# Temperature.net
KiCad netlist of a schematic drawn in Altium Designer
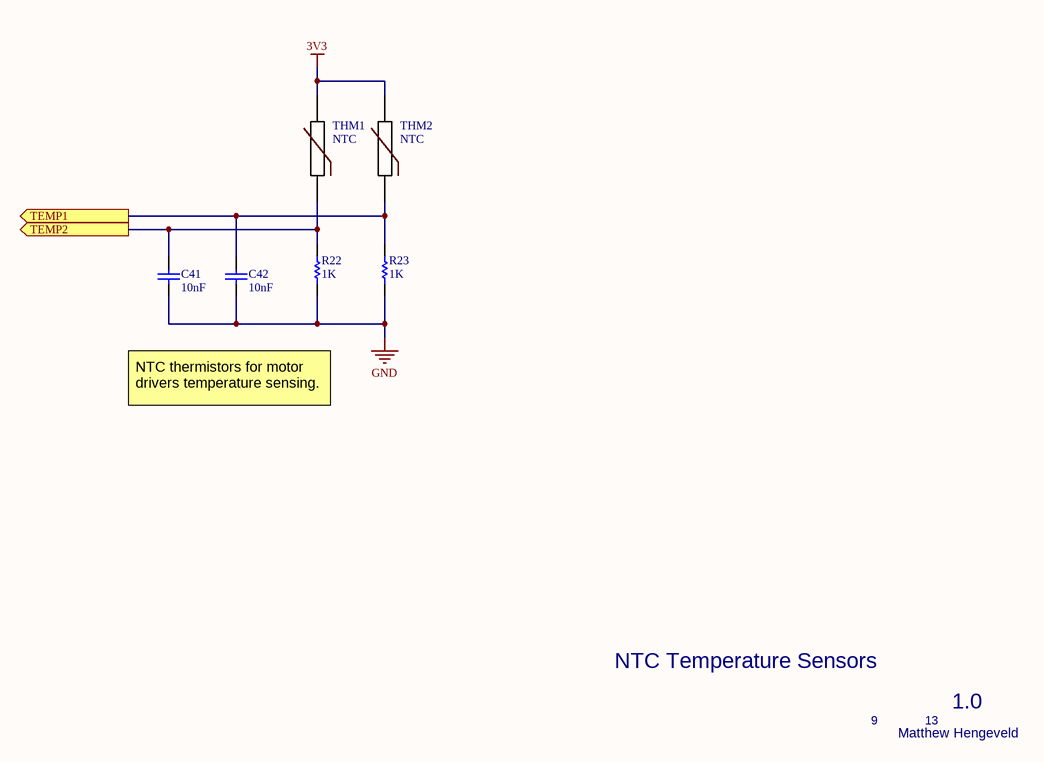
[diagram p0: Temperature.SchDoc]

(export (version "E")
  (design (tool "Eeschema 10.0.6"))
  (components
    (comp (ref "C41")
      (value "10nF")
      (footprint "CAPC1608X92X38LL15T08")
      (fields (field (name "PART NUMBER") "VJ0603Y104KNXAO") (field (name "MANUFACTURER") "Vitramon"))
      (libsource (lib "Altium Content Vault") (part "CAP"))
    )
    (comp (ref "C42")
      (value "10nF")
      (footprint "CAPC1608X92X38LL15T08")
      (fields (field (name "PART NUMBER") "VJ0603Y104KNXAO") (field (name "MANUFACTURER") "Vitramon"))
      (libsource (lib "Altium Content Vault") (part "CAP"))
    )
    (comp (ref "R22")
      (value "1K")
      (footprint "RESC1608X55X30LL15T15")
      (fields (field (name "MANUFACTURER") "Panasonic") (field (name "PART NUMBER") "ERJ-3GEYJ103V"))
      (libsource (lib "Altium Content Vault") (part "RES"))
    )
    (comp (ref "R23")
      (value "1K")
      (footprint "RESC1608X55X30LL15T15")
      (fields (field (name "MANUFACTURER") "Panasonic") (field (name "PART NUMBER") "ERJ-3GEYJ103V"))
      (libsource (lib "Altium Content Vault") (part "RES"))
    )
    (comp (ref "THM1") (value "NTC") (footprint "NTC") (libsource (lib "Hengeveld") (part "NTC")))
    (comp (ref "THM2") (value "NTC") (footprint "NTC") (libsource (lib "Hengeveld") (part "NTC")))
  )
  (nets
    (net (code "1") (name "/TEMP1") (class "Default")
      (node (ref "C42") (pin "2") (pinfunction "2_2") (pintype "passive"))
      (node (ref "R23") (pin "2") (pinfunction "2_2") (pintype "passive"))
      (node (ref "THM2") (pin "1") (pinfunction "1_1") (pintype "passive"))
    )
    (net (code "2") (name "/TEMP2") (class "Default")
      (node (ref "C41") (pin "2") (pinfunction "2_2") (pintype "passive"))
      (node (ref "R22") (pin "2") (pinfunction "2_2") (pintype "passive"))
      (node (ref "THM1") (pin "1") (pinfunction "1_1") (pintype "passive"))
    )
    (net (code "3") (name "3V3") (class "Default")
      (node (ref "THM1") (pin "2") (pinfunction "2_2") (pintype "passive"))
      (node (ref "THM2") (pin "2") (pinfunction "2_2") (pintype "passive"))
    )
    (net (code "4") (name "GND") (class "Default")
      (node (ref "C41") (pin "1") (pinfunction "1_1") (pintype "passive"))
      (node (ref "C42") (pin "1") (pinfunction "1_1") (pintype "passive"))
      (node (ref "R22") (pin "1") (pinfunction "1_1") (pintype "passive"))
      (node (ref "R23") (pin "1") (pinfunction "1_1") (pintype "passive"))
    )
  )
)
